# CompuertasNOT_Sch.net
KiCad netlist of a schematic drawn in Altium Designer
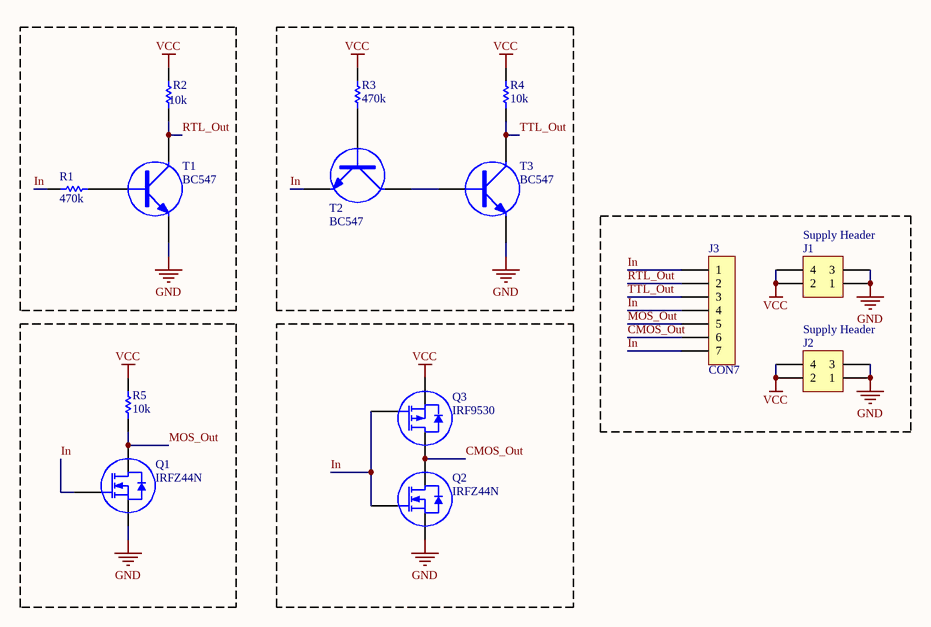
[diagram p0: CompuertasNOT_Sch.SchDoc]

(export (version "E")
  (design (tool "Eeschema 10.0.6"))
  (components
    (comp (ref "J1") (value "Supply Header") (footprint "SIP2*2") (libsource (lib "LIBEBAL") (part "CON2*2")))
    (comp (ref "J2") (value "Supply Header") (footprint "SIP2*2") (libsource (lib "LIBEBAL") (part "CON2*2")))
    (comp (ref "J3") (value "CON7") (footprint "SIP7") (libsource (lib "LIBEBAL") (part "CON7")))
    (comp (ref "Q1") (value "IRFZ44N") (footprint "TO-220 V") (libsource (lib "LIBEBAL") (part "MOSFET N")))
    (comp (ref "Q2") (value "IRFZ44N") (footprint "TO-220 V") (libsource (lib "LIBEBAL") (part "MOSFET N")))
    (comp (ref "Q3") (value "IRF9530") (footprint "TO-220 V") (libsource (lib "LIBEBAL") (part "MOSFET P")))
    (comp (ref "R1") (value "470k") (footprint "0805") (libsource (lib "LIBEBAL") (part "RES")))
    (comp (ref "R2") (value "10k") (footprint "RES400") (libsource (lib "LIBEBAL") (part "RES")))
    (comp (ref "R3") (value "470k") (footprint "RES400") (libsource (lib "LIBEBAL") (part "RES")))
    (comp (ref "R4") (value "10k") (footprint "RES400") (libsource (lib "LIBEBAL") (part "RES")))
    (comp (ref "R5") (value "10k") (footprint "RES400") (libsource (lib "LIBEBAL") (part "RES")))
    (comp (ref "T1") (value "BC547") (footprint "TO92") (libsource (lib "LIBEBAL") (part "TRANSISTOR NPN")))
    (comp (ref "T2") (value "BC547") (footprint "TO92") (libsource (lib "LIBEBAL") (part "TRANSISTOR NPN")))
    (comp (ref "T3") (value "BC547") (footprint "TO92") (libsource (lib "LIBEBAL") (part "TRANSISTOR NPN")))
  )
  (nets
    (net (code "1") (name "/CMOS_Out") (class "Default")
      (node (ref "J3") (pin "6") (pinfunction "6_6") (pintype "passive"))
      (node (ref "Q2") (pin "2") (pinfunction "D_2") (pintype "passive"))
      (node (ref "Q3") (pin "2") (pinfunction "D_2") (pintype "passive"))
    )
    (net (code "2") (name "/In") (class "Default")
      (node (ref "J3") (pin "1") (pinfunction "1_1") (pintype "passive"))
      (node (ref "J3") (pin "4") (pinfunction "4_4") (pintype "passive"))
      (node (ref "J3") (pin "7") (pinfunction "7_7") (pintype "passive"))
      (node (ref "Q1") (pin "1") (pinfunction "G_1") (pintype "passive"))
      (node (ref "Q2") (pin "1") (pinfunction "G_1") (pintype "passive"))
      (node (ref "Q3") (pin "1") (pinfunction "G_1") (pintype "passive"))
      (node (ref "R1") (pin "2") (pinfunction "2_2") (pintype "passive"))
      (node (ref "T2") (pin "3") (pinfunction "E_3") (pintype "passive"))
    )
    (net (code "3") (name "/MOS_Out") (class "Default")
      (node (ref "J3") (pin "5") (pinfunction "5_5") (pintype "passive"))
      (node (ref "Q1") (pin "2") (pinfunction "D_2") (pintype "passive"))
      (node (ref "R5") (pin "2") (pinfunction "2_2") (pintype "passive"))
    )
    (net (code "4") (name "/RTL_Out") (class "Default")
      (node (ref "J3") (pin "2") (pinfunction "2_2") (pintype "passive"))
      (node (ref "R2") (pin "1") (pinfunction "1_1") (pintype "passive"))
      (node (ref "T1") (pin "2") (pinfunction "C_2") (pintype "passive"))
    )
    (net (code "5") (name "/TTL_Out") (class "Default")
      (node (ref "J3") (pin "3") (pinfunction "3_3") (pintype "passive"))
      (node (ref "R4") (pin "1") (pinfunction "1_1") (pintype "passive"))
      (node (ref "T3") (pin "2") (pinfunction "C_2") (pintype "passive"))
    )
    (net (code "6") (name "GND") (class "Default")
      (node (ref "J1") (pin "1") (pinfunction "1_1") (pintype "passive"))
      (node (ref "J1") (pin "3") (pinfunction "3_3") (pintype "passive"))
      (node (ref "J2") (pin "1") (pinfunction "1_1") (pintype "passive"))
      (node (ref "J2") (pin "3") (pinfunction "3_3") (pintype "passive"))
      (node (ref "Q1") (pin "3") (pinfunction "S_3") (pintype "passive"))
      (node (ref "Q2") (pin "3") (pinfunction "S_3") (pintype "passive"))
      (node (ref "T1") (pin "3") (pinfunction "E_3") (pintype "passive"))
      (node (ref "T3") (pin "3") (pinfunction "E_3") (pintype "passive"))
    )
    (net (code "7") (name "Net-(T1-B)") (class "Default")
      (node (ref "R1") (pin "1") (pinfunction "1_1") (pintype "passive"))
      (node (ref "T1") (pin "1") (pinfunction "B_1") (pintype "passive"))
    )
    (net (code "8") (name "Net-(T2-B)") (class "Default")
      (node (ref "R3") (pin "1") (pinfunction "1_1") (pintype "passive"))
      (node (ref "T2") (pin "1") (pinfunction "B_1") (pintype "passive"))
    )
    (net (code "9") (name "Net-(T2-C)") (class "Default")
      (node (ref "T2") (pin "2") (pinfunction "C_2") (pintype "passive"))
      (node (ref "T3") (pin "1") (pinfunction "B_1") (pintype "passive"))
    )
    (net (code "10") (name "VCC") (class "Default")
      (node (ref "J1") (pin "2") (pinfunction "2_2") (pintype "passive"))
      (node (ref "J1") (pin "4") (pinfunction "4_4") (pintype "passive"))
      (node (ref "J2") (pin "2") (pinfunction "2_2") (pintype "passive"))
      (node (ref "J2") (pin "4") (pinfunction "4_4") (pintype "passive"))
      (node (ref "Q3") (pin "3") (pinfunction "S_3") (pintype "passive"))
      (node (ref "R2") (pin "2") (pinfunction "2_2") (pintype "passive"))
      (node (ref "R3") (pin "2") (pinfunction "2_2") (pintype "passive"))
      (node (ref "R4") (pin "2") (pinfunction "2_2") (pintype "passive"))
      (node (ref "R5") (pin "1") (pinfunction "1_1") (pintype "passive"))
    )
  )
)
